# fullSketch.net
KiCad netlist of a schematic drawn in EAGLE
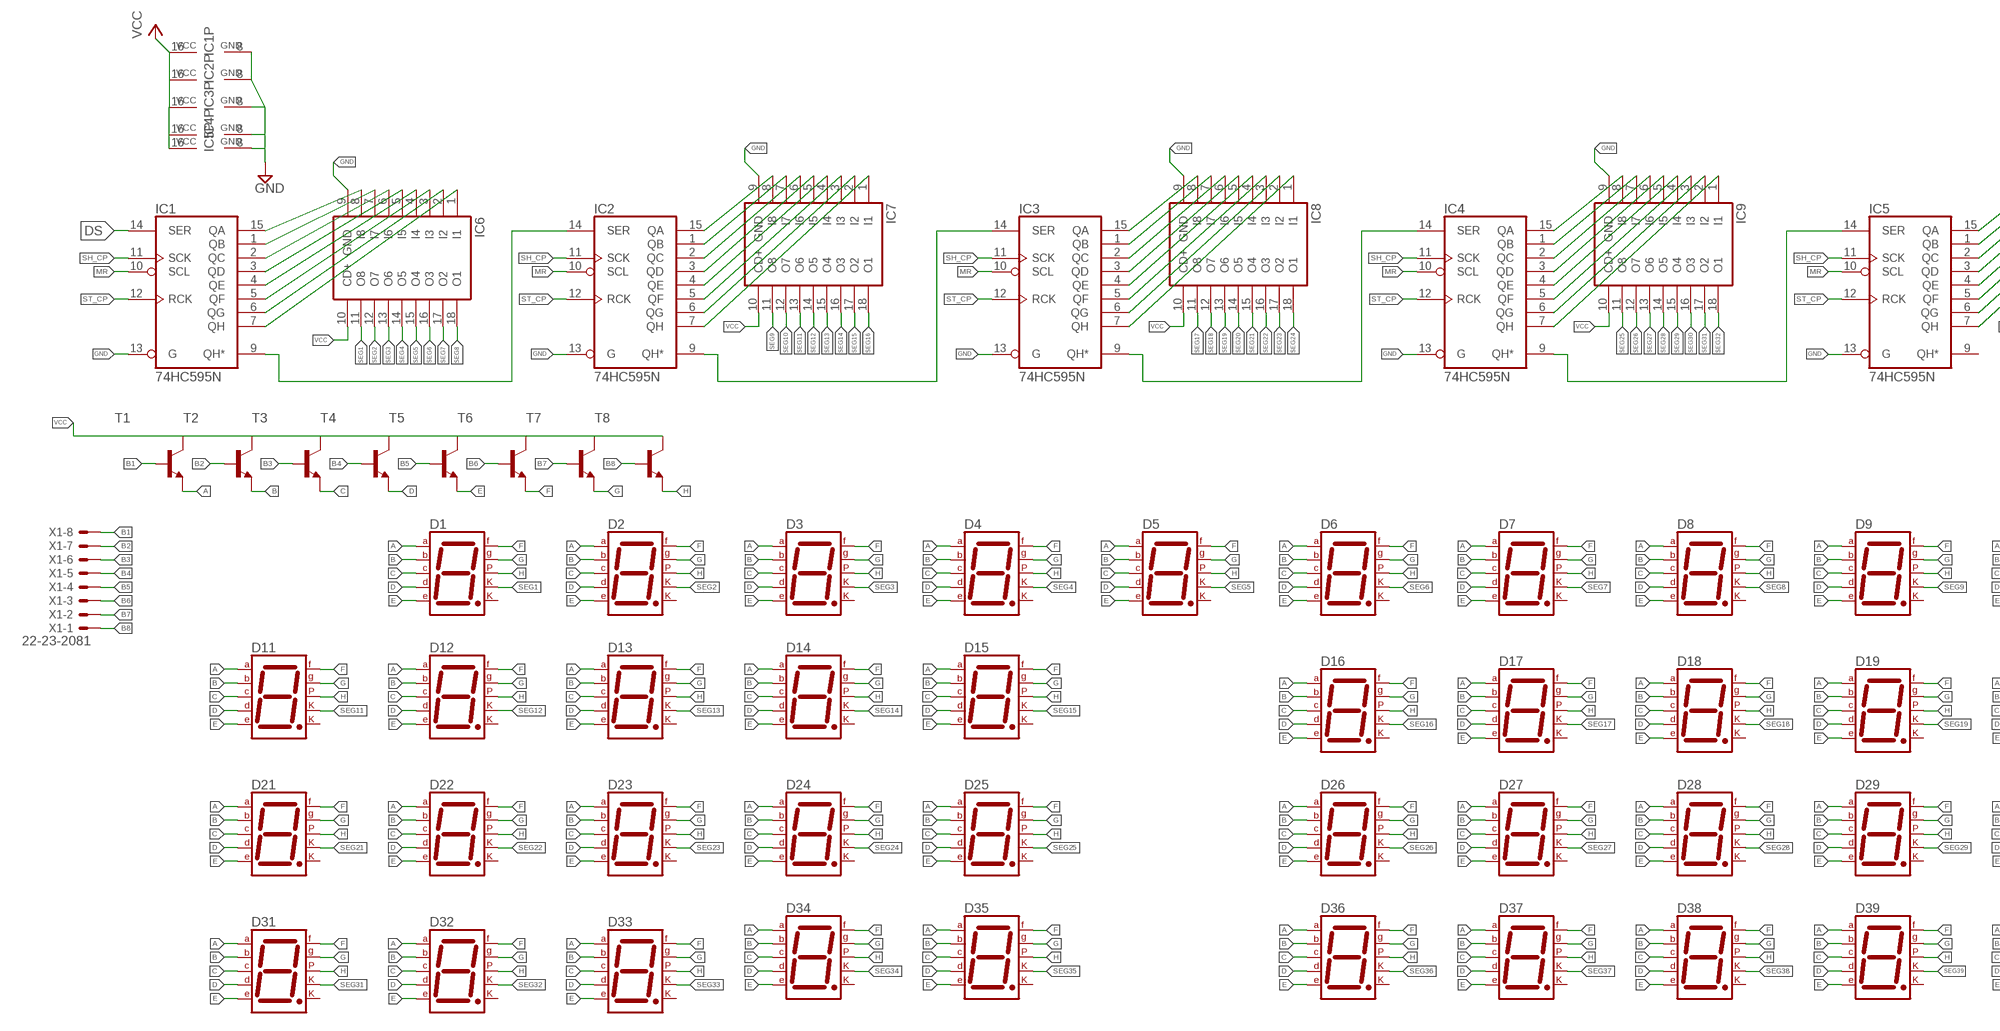
[diagram p0: schematic, sheet 1, part 1 of 2]
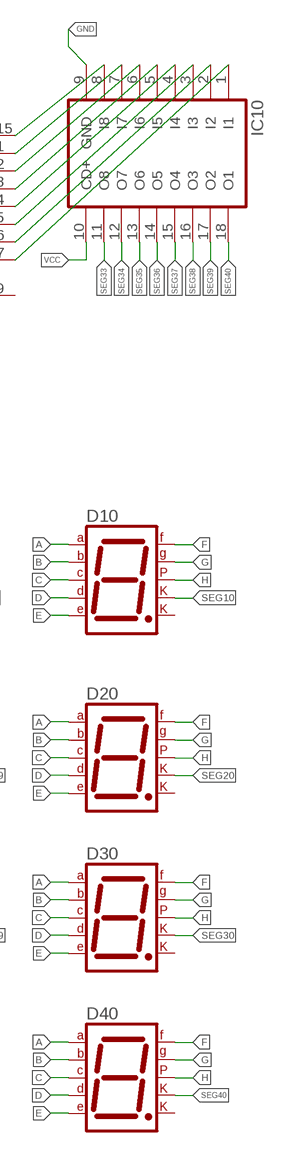
[diagram p1: schematic, sheet 1, part 2 of 2]

(export (version "E")
  (design (tool "Eeschema 10.0.6"))
  (components
    (comp (ref "D1")
      (value "7SEG-CK")
      (footprint "eagle-import:7SEG-13")
      (libsource (lib "eagle-import") (part "7SEG-CK"))
    )
    (comp (ref "D2")
      (value "7SEG-CK")
      (footprint "eagle-import:7SEG-13")
      (libsource (lib "eagle-import") (part "7SEG-CK"))
    )
    (comp (ref "D3")
      (value "7SEG-CK")
      (footprint "eagle-import:7SEG-13")
      (libsource (lib "eagle-import") (part "7SEG-CK"))
    )
    (comp (ref "D4")
      (value "7SEG-CK")
      (footprint "eagle-import:7SEG-13")
      (libsource (lib "eagle-import") (part "7SEG-CK"))
    )
    (comp (ref "D5")
      (value "7SEG-CK")
      (footprint "eagle-import:7SEG-13")
      (libsource (lib "eagle-import") (part "7SEG-CK"))
    )
    (comp (ref "D6")
      (value "7SEG-CK")
      (footprint "eagle-import:7SEG-13")
      (libsource (lib "eagle-import") (part "7SEG-CK"))
    )
    (comp (ref "D7")
      (value "7SEG-CK")
      (footprint "eagle-import:7SEG-13")
      (libsource (lib "eagle-import") (part "7SEG-CK"))
    )
    (comp (ref "D8")
      (value "7SEG-CK")
      (footprint "eagle-import:7SEG-13")
      (libsource (lib "eagle-import") (part "7SEG-CK"))
    )
    (comp (ref "D9")
      (value "7SEG-CK")
      (footprint "eagle-import:7SEG-13")
      (libsource (lib "eagle-import") (part "7SEG-CK"))
    )
    (comp (ref "D10")
      (value "7SEG-CK")
      (footprint "eagle-import:7SEG-13")
      (libsource (lib "eagle-import") (part "7SEG-CK"))
    )
    (comp (ref "D11")
      (value "7SEG-CK")
      (footprint "eagle-import:7SEG-13")
      (libsource (lib "eagle-import") (part "7SEG-CK"))
    )
    (comp (ref "D12")
      (value "7SEG-CK")
      (footprint "eagle-import:7SEG-13")
      (libsource (lib "eagle-import") (part "7SEG-CK"))
    )
    (comp (ref "D13")
      (value "7SEG-CK")
      (footprint "eagle-import:7SEG-13")
      (libsource (lib "eagle-import") (part "7SEG-CK"))
    )
    (comp (ref "D14")
      (value "7SEG-CK")
      (footprint "eagle-import:7SEG-13")
      (libsource (lib "eagle-import") (part "7SEG-CK"))
    )
    (comp (ref "D15")
      (value "7SEG-CK")
      (footprint "eagle-import:7SEG-13")
      (libsource (lib "eagle-import") (part "7SEG-CK"))
    )
    (comp (ref "D16")
      (value "7SEG-CK")
      (footprint "eagle-import:7SEG-13")
      (libsource (lib "eagle-import") (part "7SEG-CK"))
    )
    (comp (ref "D17")
      (value "7SEG-CK")
      (footprint "eagle-import:7SEG-13")
      (libsource (lib "eagle-import") (part "7SEG-CK"))
    )
    (comp (ref "D18")
      (value "7SEG-CK")
      (footprint "eagle-import:7SEG-13")
      (libsource (lib "eagle-import") (part "7SEG-CK"))
    )
    (comp (ref "D19")
      (value "7SEG-CK")
      (footprint "eagle-import:7SEG-13")
      (libsource (lib "eagle-import") (part "7SEG-CK"))
    )
    (comp (ref "D20")
      (value "7SEG-CK")
      (footprint "eagle-import:7SEG-13")
      (libsource (lib "eagle-import") (part "7SEG-CK"))
    )
    (comp (ref "D21")
      (value "7SEG-CK")
      (footprint "eagle-import:7SEG-13")
      (libsource (lib "eagle-import") (part "7SEG-CK"))
    )
    (comp (ref "D22")
      (value "7SEG-CK")
      (footprint "eagle-import:7SEG-13")
      (libsource (lib "eagle-import") (part "7SEG-CK"))
    )
    (comp (ref "D23")
      (value "7SEG-CK")
      (footprint "eagle-import:7SEG-13")
      (libsource (lib "eagle-import") (part "7SEG-CK"))
    )
    (comp (ref "D24")
      (value "7SEG-CK")
      (footprint "eagle-import:7SEG-13")
      (libsource (lib "eagle-import") (part "7SEG-CK"))
    )
    (comp (ref "D25")
      (value "7SEG-CK")
      (footprint "eagle-import:7SEG-13")
      (libsource (lib "eagle-import") (part "7SEG-CK"))
    )
    (comp (ref "D26")
      (value "7SEG-CK")
      (footprint "eagle-import:7SEG-13")
      (libsource (lib "eagle-import") (part "7SEG-CK"))
    )
    (comp (ref "D27")
      (value "7SEG-CK")
      (footprint "eagle-import:7SEG-13")
      (libsource (lib "eagle-import") (part "7SEG-CK"))
    )
    (comp (ref "D28")
      (value "7SEG-CK")
      (footprint "eagle-import:7SEG-13")
      (libsource (lib "eagle-import") (part "7SEG-CK"))
    )
    (comp (ref "D29")
      (value "7SEG-CK")
      (footprint "eagle-import:7SEG-13")
      (libsource (lib "eagle-import") (part "7SEG-CK"))
    )
    (comp (ref "D30")
      (value "7SEG-CK")
      (footprint "eagle-import:7SEG-13")
      (libsource (lib "eagle-import") (part "7SEG-CK"))
    )
    (comp (ref "D31")
      (value "7SEG-CK")
      (footprint "eagle-import:7SEG-13")
      (libsource (lib "eagle-import") (part "7SEG-CK"))
    )
    (comp (ref "D32")
      (value "7SEG-CK")
      (footprint "eagle-import:7SEG-13")
      (libsource (lib "eagle-import") (part "7SEG-CK"))
    )
    (comp (ref "D33")
      (value "7SEG-CK")
      (footprint "eagle-import:7SEG-13")
      (libsource (lib "eagle-import") (part "7SEG-CK"))
    )
    (comp (ref "D34")
      (value "7SEG-CK")
      (footprint "eagle-import:7SEG-13")
      (libsource (lib "eagle-import") (part "7SEG-CK"))
    )
    (comp (ref "D35")
      (value "7SEG-CK")
      (footprint "eagle-import:7SEG-13")
      (libsource (lib "eagle-import") (part "7SEG-CK"))
    )
    (comp (ref "D36")
      (value "7SEG-CK")
      (footprint "eagle-import:7SEG-13")
      (libsource (lib "eagle-import") (part "7SEG-CK"))
    )
    (comp (ref "D37")
      (value "7SEG-CK")
      (footprint "eagle-import:7SEG-13")
      (libsource (lib "eagle-import") (part "7SEG-CK"))
    )
    (comp (ref "D38")
      (value "7SEG-CK")
      (footprint "eagle-import:7SEG-13")
      (libsource (lib "eagle-import") (part "7SEG-CK"))
    )
    (comp (ref "D39")
      (value "7SEG-CK")
      (footprint "eagle-import:7SEG-13")
      (libsource (lib "eagle-import") (part "7SEG-CK"))
    )
    (comp (ref "D40")
      (value "7SEG-CK")
      (footprint "eagle-import:7SEG-13")
      (libsource (lib "eagle-import") (part "7SEG-CK"))
    )
    (comp (ref "IC1")
      (value "74HC595N")
      (footprint "eagle-import:DIL16")
      (libsource (lib "eagle-import") (part "74595NHC"))
    )
    (comp (ref "IC2")
      (value "74HC595N")
      (footprint "eagle-import:DIL16")
      (libsource (lib "eagle-import") (part "74595NHC"))
    )
    (comp (ref "IC3")
      (value "74HC595N")
      (footprint "eagle-import:DIL16")
      (libsource (lib "eagle-import") (part "74595NHC"))
    )
    (comp (ref "IC4")
      (value "74HC595N")
      (footprint "eagle-import:DIL16")
      (libsource (lib "eagle-import") (part "74595NHC"))
    )
    (comp (ref "IC5")
      (value "74HC595N")
      (footprint "eagle-import:DIL16")
      (libsource (lib "eagle-import") (part "74595NHC"))
    )
    (comp (ref "IC6")
      (value "ULN2803A")
      (footprint "eagle-import:DIL18")
      (libsource (lib "eagle-import") (part "ULN2803A"))
    )
    (comp (ref "IC7")
      (value "ULN2803A")
      (footprint "eagle-import:DIL18")
      (libsource (lib "eagle-import") (part "ULN2803A"))
    )
    (comp (ref "IC8")
      (value "ULN2803A")
      (footprint "eagle-import:DIL18")
      (libsource (lib "eagle-import") (part "ULN2803A"))
    )
    (comp (ref "IC9")
      (value "ULN2803A")
      (footprint "eagle-import:DIL18")
      (libsource (lib "eagle-import") (part "ULN2803A"))
    )
    (comp (ref "IC10")
      (value "ULN2803A")
      (footprint "eagle-import:DIL18")
      (libsource (lib "eagle-import") (part "ULN2803A"))
    )
    (comp (ref "T1")
      (value "-NPN-TO92")
      (footprint "eagle-import:TO92")
      (libsource (lib "eagle-import") (part "-NPN-TO92"))
    )
    (comp (ref "T2")
      (value "-NPN-TO92")
      (footprint "eagle-import:TO92")
      (libsource (lib "eagle-import") (part "-NPN-TO92"))
    )
    (comp (ref "T3")
      (value "-NPN-TO92")
      (footprint "eagle-import:TO92")
      (libsource (lib "eagle-import") (part "-NPN-TO92"))
    )
    (comp (ref "T4")
      (value "-NPN-TO92")
      (footprint "eagle-import:TO92")
      (libsource (lib "eagle-import") (part "-NPN-TO92"))
    )
    (comp (ref "T5")
      (value "-NPN-TO92")
      (footprint "eagle-import:TO92")
      (libsource (lib "eagle-import") (part "-NPN-TO92"))
    )
    (comp (ref "T6")
      (value "-NPN-TO92")
      (footprint "eagle-import:TO92")
      (libsource (lib "eagle-import") (part "-NPN-TO92"))
    )
    (comp (ref "T7")
      (value "-NPN-TO92")
      (footprint "eagle-import:TO92")
      (libsource (lib "eagle-import") (part "-NPN-TO92"))
    )
    (comp (ref "T8")
      (value "-NPN-TO92")
      (footprint "eagle-import:TO92")
      (libsource (lib "eagle-import") (part "-NPN-TO92"))
    )
    (comp (ref "X1")
      (value "22-23-2081")
      (footprint "eagle-import:22-23-2081")
      (fields (field (name "MF") "MOLEX"))
      (libsource (lib "eagle-import") (part "22-23-2081"))
    )
  )
  (nets
    (net (code "1") (name "A") (class "Default")
      (node (ref "D1") (pin "7") (pinfunction "A_7") (pintype "passive"))
      (node (ref "D10") (pin "7") (pinfunction "A_7") (pintype "passive"))
      (node (ref "D11") (pin "7") (pinfunction "A_7") (pintype "passive"))
      (node (ref "D12") (pin "7") (pinfunction "A_7") (pintype "passive"))
      (node (ref "D13") (pin "7") (pinfunction "A_7") (pintype "passive"))
      (node (ref "D14") (pin "7") (pinfunction "A_7") (pintype "passive"))
      (node (ref "D15") (pin "7") (pinfunction "A_7") (pintype "passive"))
      (node (ref "D16") (pin "7") (pinfunction "A_7") (pintype "passive"))
      (node (ref "D17") (pin "7") (pinfunction "A_7") (pintype "passive"))
      (node (ref "D18") (pin "7") (pinfunction "A_7") (pintype "passive"))
      (node (ref "D19") (pin "7") (pinfunction "A_7") (pintype "passive"))
      (node (ref "D2") (pin "7") (pinfunction "A_7") (pintype "passive"))
      (node (ref "D20") (pin "7") (pinfunction "A_7") (pintype "passive"))
      (node (ref "D21") (pin "7") (pinfunction "A_7") (pintype "passive"))
      (node (ref "D22") (pin "7") (pinfunction "A_7") (pintype "passive"))
      (node (ref "D23") (pin "7") (pinfunction "A_7") (pintype "passive"))
      (node (ref "D24") (pin "7") (pinfunction "A_7") (pintype "passive"))
      (node (ref "D25") (pin "7") (pinfunction "A_7") (pintype "passive"))
      (node (ref "D26") (pin "7") (pinfunction "A_7") (pintype "passive"))
      (node (ref "D27") (pin "7") (pinfunction "A_7") (pintype "passive"))
      (node (ref "D28") (pin "7") (pinfunction "A_7") (pintype "passive"))
      (node (ref "D29") (pin "7") (pinfunction "A_7") (pintype "passive"))
      (node (ref "D3") (pin "7") (pinfunction "A_7") (pintype "passive"))
      (node (ref "D30") (pin "7") (pinfunction "A_7") (pintype "passive"))
      (node (ref "D31") (pin "7") (pinfunction "A_7") (pintype "passive"))
      (node (ref "D32") (pin "7") (pinfunction "A_7") (pintype "passive"))
      (node (ref "D33") (pin "7") (pinfunction "A_7") (pintype "passive"))
      (node (ref "D34") (pin "7") (pinfunction "A_7") (pintype "passive"))
      (node (ref "D35") (pin "7") (pinfunction "A_7") (pintype "passive"))
      (node (ref "D36") (pin "7") (pinfunction "A_7") (pintype "passive"))
      (node (ref "D37") (pin "7") (pinfunction "A_7") (pintype "passive"))
      (node (ref "D38") (pin "7") (pinfunction "A_7") (pintype "passive"))
      (node (ref "D39") (pin "7") (pinfunction "A_7") (pintype "passive"))
      (node (ref "D4") (pin "7") (pinfunction "A_7") (pintype "passive"))
      (node (ref "D40") (pin "7") (pinfunction "A_7") (pintype "passive"))
      (node (ref "D5") (pin "7") (pinfunction "A_7") (pintype "passive"))
      (node (ref "D6") (pin "7") (pinfunction "A_7") (pintype "passive"))
      (node (ref "D7") (pin "7") (pinfunction "A_7") (pintype "passive"))
      (node (ref "D8") (pin "7") (pinfunction "A_7") (pintype "passive"))
      (node (ref "D9") (pin "7") (pinfunction "A_7") (pintype "passive"))
      (node (ref "T1") (pin "1") (pinfunction "E_1") (pintype "passive"))
    )
    (net (code "2") (name "B") (class "Default")
      (node (ref "D1") (pin "6") (pinfunction "B_6") (pintype "passive"))
      (node (ref "D10") (pin "6") (pinfunction "B_6") (pintype "passive"))
      (node (ref "D11") (pin "6") (pinfunction "B_6") (pintype "passive"))
      (node (ref "D12") (pin "6") (pinfunction "B_6") (pintype "passive"))
      (node (ref "D13") (pin "6") (pinfunction "B_6") (pintype "passive"))
      (node (ref "D14") (pin "6") (pinfunction "B_6") (pintype "passive"))
      (node (ref "D15") (pin "6") (pinfunction "B_6") (pintype "passive"))
      (node (ref "D16") (pin "6") (pinfunction "B_6") (pintype "passive"))
      (node (ref "D17") (pin "6") (pinfunction "B_6") (pintype "passive"))
      (node (ref "D18") (pin "6") (pinfunction "B_6") (pintype "passive"))
      (node (ref "D19") (pin "6") (pinfunction "B_6") (pintype "passive"))
      (node (ref "D2") (pin "6") (pinfunction "B_6") (pintype "passive"))
      (node (ref "D20") (pin "6") (pinfunction "B_6") (pintype "passive"))
      (node (ref "D21") (pin "6") (pinfunction "B_6") (pintype "passive"))
      (node (ref "D22") (pin "6") (pinfunction "B_6") (pintype "passive"))
      (node (ref "D23") (pin "6") (pinfunction "B_6") (pintype "passive"))
      (node (ref "D24") (pin "6") (pinfunction "B_6") (pintype "passive"))
      (node (ref "D25") (pin "6") (pinfunction "B_6") (pintype "passive"))
      (node (ref "D26") (pin "6") (pinfunction "B_6") (pintype "passive"))
      (node (ref "D27") (pin "6") (pinfunction "B_6") (pintype "passive"))
      (node (ref "D28") (pin "6") (pinfunction "B_6") (pintype "passive"))
      (node (ref "D29") (pin "6") (pinfunction "B_6") (pintype "passive"))
      (node (ref "D3") (pin "6") (pinfunction "B_6") (pintype "passive"))
      (node (ref "D30") (pin "6") (pinfunction "B_6") (pintype "passive"))
      (node (ref "D31") (pin "6") (pinfunction "B_6") (pintype "passive"))
      (node (ref "D32") (pin "6") (pinfunction "B_6") (pintype "passive"))
      (node (ref "D33") (pin "6") (pinfunction "B_6") (pintype "passive"))
      (node (ref "D34") (pin "6") (pinfunction "B_6") (pintype "passive"))
      (node (ref "D35") (pin "6") (pinfunction "B_6") (pintype "passive"))
      (node (ref "D36") (pin "6") (pinfunction "B_6") (pintype "passive"))
      (node (ref "D37") (pin "6") (pinfunction "B_6") (pintype "passive"))
      (node (ref "D38") (pin "6") (pinfunction "B_6") (pintype "passive"))
      (node (ref "D39") (pin "6") (pinfunction "B_6") (pintype "passive"))
      (node (ref "D4") (pin "6") (pinfunction "B_6") (pintype "passive"))
      (node (ref "D40") (pin "6") (pinfunction "B_6") (pintype "passive"))
      (node (ref "D5") (pin "6") (pinfunction "B_6") (pintype "passive"))
      (node (ref "D6") (pin "6") (pinfunction "B_6") (pintype "passive"))
      (node (ref "D7") (pin "6") (pinfunction "B_6") (pintype "passive"))
      (node (ref "D8") (pin "6") (pinfunction "B_6") (pintype "passive"))
      (node (ref "D9") (pin "6") (pinfunction "B_6") (pintype "passive"))
      (node (ref "T2") (pin "1") (pinfunction "E_1") (pintype "passive"))
    )
    (net (code "3") (name "B1") (class "Default")
      (node (ref "T1") (pin "2") (pinfunction "B_2") (pintype "passive"))
      (node (ref "X1") (pin "8") (pinfunction "S_8") (pintype "passive"))
    )
    (net (code "4") (name "B2") (class "Default")
      (node (ref "T2") (pin "2") (pinfunction "B_2") (pintype "passive"))
      (node (ref "X1") (pin "7") (pinfunction "S_7") (pintype "passive"))
    )
    (net (code "5") (name "B3") (class "Default")
      (node (ref "T3") (pin "2") (pinfunction "B_2") (pintype "passive"))
      (node (ref "X1") (pin "6") (pinfunction "S_6") (pintype "passive"))
    )
    (net (code "6") (name "B4") (class "Default")
      (node (ref "T4") (pin "2") (pinfunction "B_2") (pintype "passive"))
      (node (ref "X1") (pin "5") (pinfunction "S_5") (pintype "passive"))
    )
    (net (code "7") (name "B5") (class "Default")
      (node (ref "T5") (pin "2") (pinfunction "B_2") (pintype "passive"))
      (node (ref "X1") (pin "4") (pinfunction "S_4") (pintype "passive"))
    )
    (net (code "8") (name "B6") (class "Default")
      (node (ref "T6") (pin "2") (pinfunction "B_2") (pintype "passive"))
      (node (ref "X1") (pin "3") (pinfunction "S_3") (pintype "passive"))
    )
    (net (code "9") (name "B7") (class "Default")
      (node (ref "T7") (pin "2") (pinfunction "B_2") (pintype "passive"))
      (node (ref "X1") (pin "2") (pinfunction "S_2") (pintype "passive"))
    )
    (net (code "10") (name "B8") (class "Default")
      (node (ref "T8") (pin "2") (pinfunction "B_2") (pintype "passive"))
      (node (ref "X1") (pin "1") (pinfunction "S_1") (pintype "passive"))
    )
    (net (code "11") (name "C") (class "Default")
      (node (ref "D1") (pin "4") (pinfunction "C_4") (pintype "passive"))
      (node (ref "D10") (pin "4") (pinfunction "C_4") (pintype "passive"))
      (node (ref "D11") (pin "4") (pinfunction "C_4") (pintype "passive"))
      (node (ref "D12") (pin "4") (pinfunction "C_4") (pintype "passive"))
      (node (ref "D13") (pin "4") (pinfunction "C_4") (pintype "passive"))
      (node (ref "D14") (pin "4") (pinfunction "C_4") (pintype "passive"))
      (node (ref "D15") (pin "4") (pinfunction "C_4") (pintype "passive"))
      (node (ref "D16") (pin "4") (pinfunction "C_4") (pintype "passive"))
      (node (ref "D17") (pin "4") (pinfunction "C_4") (pintype "passive"))
      (node (ref "D18") (pin "4") (pinfunction "C_4") (pintype "passive"))
      (node (ref "D19") (pin "4") (pinfunction "C_4") (pintype "passive"))
      (node (ref "D2") (pin "4") (pinfunction "C_4") (pintype "passive"))
      (node (ref "D20") (pin "4") (pinfunction "C_4") (pintype "passive"))
      (node (ref "D21") (pin "4") (pinfunction "C_4") (pintype "passive"))
      (node (ref "D22") (pin "4") (pinfunction "C_4") (pintype "passive"))
      (node (ref "D23") (pin "4") (pinfunction "C_4") (pintype "passive"))
      (node (ref "D24") (pin "4") (pinfunction "C_4") (pintype "passive"))
      (node (ref "D25") (pin "4") (pinfunction "C_4") (pintype "passive"))
      (node (ref "D26") (pin "4") (pinfunction "C_4") (pintype "passive"))
      (node (ref "D27") (pin "4") (pinfunction "C_4") (pintype "passive"))
      (node (ref "D28") (pin "4") (pinfunction "C_4") (pintype "passive"))
      (node (ref "D29") (pin "4") (pinfunction "C_4") (pintype "passive"))
      (node (ref "D3") (pin "4") (pinfunction "C_4") (pintype "passive"))
      (node (ref "D30") (pin "4") (pinfunction "C_4") (pintype "passive"))
      (node (ref "D31") (pin "4") (pinfunction "C_4") (pintype "passive"))
      (node (ref "D32") (pin "4") (pinfunction "C_4") (pintype "passive"))
      (node (ref "D33") (pin "4") (pinfunction "C_4") (pintype "passive"))
      (node (ref "D34") (pin "4") (pinfunction "C_4") (pintype "passive"))
      (node (ref "D35") (pin "4") (pinfunction "C_4") (pintype "passive"))
      (node (ref "D36") (pin "4") (pinfunction "C_4") (pintype "passive"))
      (node (ref "D37") (pin "4") (pinfunction "C_4") (pintype "passive"))
      (node (ref "D38") (pin "4") (pinfunction "C_4") (pintype "passive"))
      (node (ref "D39") (pin "4") (pinfunction "C_4") (pintype "passive"))
      (node (ref "D4") (pin "4") (pinfunction "C_4") (pintype "passive"))
      (node (ref "D40") (pin "4") (pinfunction "C_4") (pintype "passive"))
      (node (ref "D5") (pin "4") (pinfunction "C_4") (pintype "passive"))
      (node (ref "D6") (pin "4") (pinfunction "C_4") (pintype "passive"))
      (node (ref "D7") (pin "4") (pinfunction "C_4") (pintype "passive"))
      (node (ref "D8") (pin "4") (pinfunction "C_4") (pintype "passive"))
      (node (ref "D9") (pin "4") (pinfunction "C_4") (pintype "passive"))
      (node (ref "T3") (pin "1") (pinfunction "E_1") (pintype "passive"))
    )
    (net (code "12") (name "D") (class "Default")
      (node (ref "D1") (pin "2") (pinfunction "D_2") (pintype "passive"))
      (node (ref "D10") (pin "2") (pinfunction "D_2") (pintype "passive"))
      (node (ref "D11") (pin "2") (pinfunction "D_2") (pintype "passive"))
      (node (ref "D12") (pin "2") (pinfunction "D_2") (pintype "passive"))
      (node (ref "D13") (pin "2") (pinfunction "D_2") (pintype "passive"))
      (node (ref "D14") (pin "2") (pinfunction "D_2") (pintype "passive"))
      (node (ref "D15") (pin "2") (pinfunction "D_2") (pintype "passive"))
      (node (ref "D16") (pin "2") (pinfunction "D_2") (pintype "passive"))
      (node (ref "D17") (pin "2") (pinfunction "D_2") (pintype "passive"))
      (node (ref "D18") (pin "2") (pinfunction "D_2") (pintype "passive"))
      (node (ref "D19") (pin "2") (pinfunction "D_2") (pintype "passive"))
      (node (ref "D2") (pin "2") (pinfunction "D_2") (pintype "passive"))
      (node (ref "D20") (pin "2") (pinfunction "D_2") (pintype "passive"))
      (node (ref "D21") (pin "2") (pinfunction "D_2") (pintype "passive"))
      (node (ref "D22") (pin "2") (pinfunction "D_2") (pintype "passive"))
      (node (ref "D23") (pin "2") (pinfunction "D_2") (pintype "passive"))
      (node (ref "D24") (pin "2") (pinfunction "D_2") (pintype "passive"))
      (node (ref "D25") (pin "2") (pinfunction "D_2") (pintype "passive"))
      (node (ref "D26") (pin "2") (pinfunction "D_2") (pintype "passive"))
      (node (ref "D27") (pin "2") (pinfunction "D_2") (pintype "passive"))
      (node (ref "D28") (pin "2") (pinfunction "D_2") (pintype "passive"))
      (node (ref "D29") (pin "2") (pinfunction "D_2") (pintype "passive"))
      (node (ref "D3") (pin "2") (pinfunction "D_2") (pintype "passive"))
      (node (ref "D30") (pin "2") (pinfunction "D_2") (pintype "passive"))
      (node (ref "D31") (pin "2") (pinfunction "D_2") (pintype "passive"))
      (node (ref "D32") (pin "2") (pinfunction "D_2") (pintype "passive"))
      (node (ref "D33") (pin "2") (pinfunction "D_2") (pintype "passive"))
      (node (ref "D34") (pin "2") (pinfunction "D_2") (pintype "passive"))
      (node (ref "D35") (pin "2") (pinfunction "D_2") (pintype "passive"))
      (node (ref "D36") (pin "2") (pinfunction "D_2") (pintype "passive"))
      (node (ref "D37") (pin "2") (pinfunction "D_2") (pintype "passive"))
      (node (ref "D38") (pin "2") (pinfunction "D_2") (pintype "passive"))
      (node (ref "D39") (pin "2") (pinfunction "D_2") (pintype "passive"))
      (node (ref "D4") (pin "2") (pinfunction "D_2") (pintype "passive"))
      (node (ref "D40") (pin "2") (pinfunction "D_2") (pintype "passive"))
      (node (ref "D5") (pin "2") (pinfunction "D_2") (pintype "passive"))
      (node (ref "D6") (pin "2") (pinfunction "D_2") (pintype "passive"))
      (node (ref "D7") (pin "2") (pinfunction "D_2") (pintype "passive"))
      (node (ref "D8") (pin "2") (pinfunction "D_2") (pintype "passive"))
      (node (ref "D9") (pin "2") (pinfunction "D_2") (pintype "passive"))
      (node (ref "T4") (pin "1") (pinfunction "E_1") (pintype "passive"))
    )
    (net (code "13") (name "DS") (class "Default")
      (node (ref "IC1") (pin "14") (pinfunction "SER_14") (pintype "input"))
    )
    (net (code "14") (name "E") (class "Default")
      (node (ref "D1") (pin "1") (pinfunction "E_1") (pintype "passive"))
      (node (ref "D10") (pin "1") (pinfunction "E_1") (pintype "passive"))
      (node (ref "D11") (pin "1") (pinfunction "E_1") (pintype "passive"))
      (node (ref "D12") (pin "1") (pinfunction "E_1") (pintype "passive"))
      (node (ref "D13") (pin "1") (pinfunction "E_1") (pintype "passive"))
      (node (ref "D14") (pin "1") (pinfunction "E_1") (pintype "passive"))
      (node (ref "D15") (pin "1") (pinfunction "E_1") (pintype "passive"))
      (node (ref "D16") (pin "1") (pinfunction "E_1") (pintype "passive"))
      (node (ref "D17") (pin "1") (pinfunction "E_1") (pintype "passive"))
      (node (ref "D18") (pin "1") (pinfunction "E_1") (pintype "passive"))
      (node (ref "D19") (pin "1") (pinfunction "E_1") (pintype "passive"))
      (node (ref "D2") (pin "1") (pinfunction "E_1") (pintype "passive"))
      (node (ref "D20") (pin "1") (pinfunction "E_1") (pintype "passive"))
      (node (ref "D21") (pin "1") (pinfunction "E_1") (pintype "passive"))
      (node (ref "D22") (pin "1") (pinfunction "E_1") (pintype "passive"))
      (node (ref "D23") (pin "1") (pinfunction "E_1") (pintype "passive"))
      (node (ref "D24") (pin "1") (pinfunction "E_1") (pintype "passive"))
      (node (ref "D25") (pin "1") (pinfunction "E_1") (pintype "passive"))
      (node (ref "D26") (pin "1") (pinfunction "E_1") (pintype "passive"))
      (node (ref "D27") (pin "1") (pinfunction "E_1") (pintype "passive"))
      (node (ref "D28") (pin "1") (pinfunction "E_1") (pintype "passive"))
      (node (ref "D29") (pin "1") (pinfunction "E_1") (pintype "passive"))
      (node (ref "D3") (pin "1") (pinfunction "E_1") (pintype "passive"))
      (node (ref "D30") (pin "1") (pinfunction "E_1") (pintype "passive"))
      (node (ref "D31") (pin "1") (pinfunction "E_1") (pintype "passive"))
      (node (ref "D32") (pin "1") (pinfunction "E_1") (pintype "passive"))
      (node (ref "D33") (pin "1") (pinfunction "E_1") (pintype "passive"))
      (node (ref "D34") (pin "1") (pinfunction "E_1") (pintype "passive"))
      (node (ref "D35") (pin "1") (pinfunction "E_1") (pintype "passive"))
      (node (ref "D36") (pin "1") (pinfunction "E_1") (pintype "passive"))
      (node (ref "D37") (pin "1") (pinfunction "E_1") (pintype "passive"))
      (node (ref "D38") (pin "1") (pinfunction "E_1") (pintype "passive"))
      (node (ref "D39") (pin "1") (pinfunction "E_1") (pintype "passive"))
      (node (ref "D4") (pin "1") (pinfunction "E_1") (pintype "passive"))
      (node (ref "D40") (pin "1") (pinfunction "E_1") (pintype "passive"))
      (node (ref "D5") (pin "1") (pinfunction "E_1") (pintype "passive"))
      (node (ref "D6") (pin "1") (pinfunction "E_1") (pintype "passive"))
      (node (ref "D7") (pin "1") (pinfunction "E_1") (pintype "passive"))
      (node (ref "D8") (pin "1") (pinfunction "E_1") (pintype "passive"))
      (node (ref "D9") (pin "1") (pinfunction "E_1") (pintype "passive"))
      (node (ref "T5") (pin "1") (pinfunction "E_1") (pintype "passive"))
    )
    (net (code "15") (name "F") (class "Default")
      (node (ref "D1") (pin "9") (pinfunction "F_9") (pintype "passive"))
      (node (ref "D10") (pin "9") (pinfunction "F_9") (pintype "passive"))
      (node (ref "D11") (pin "9") (pinfunction "F_9") (pintype "passive"))
      (node (ref "D12") (pin "9") (pinfunction "F_9") (pintype "passive"))
      (node (ref "D13") (pin "9") (pinfunction "F_9") (pintype "passive"))
      (node (ref "D14") (pin "9") (pinfunction "F_9") (pintype "passive"))
      (node (ref "D15") (pin "9") (pinfunction "F_9") (pintype "passive"))
      (node (ref "D16") (pin "9") (pinfunction "F_9") (pintype "passive"))
      (node (ref "D17") (pin "9") (pinfunction "F_9") (pintype "passive"))
      (node (ref "D18") (pin "9") (pinfunction "F_9") (pintype "passive"))
      (node (ref "D19") (pin "9") (pinfunction "F_9") (pintype "passive"))
      (node (ref "D2") (pin "9") (pinfunction "F_9") (pintype "passive"))
      (node (ref "D20") (pin "9") (pinfunction "F_9") (pintype "passive"))
      (node (ref "D21") (pin "9") (pinfunction "F_9") (pintype "passive"))
      (node (ref "D22") (pin "9") (pinfunction "F_9") (pintype "passive"))
      (node (ref "D23") (pin "9") (pinfunction "F_9") (pintype "passive"))
      (node (ref "D24") (pin "9") (pinfunction "F_9") (pintype "passive"))
      (node (ref "D25") (pin "9") (pinfunction "F_9") (pintype "passive"))
      (node (ref "D26") (pin "9") (pinfunction "F_9") (pintype "passive"))
      (node (ref "D27") (pin "9") (pinfunction "F_9") (pintype "passive"))
      (node (ref "D28") (pin "9") (pinfunction "F_9") (pintype "passive"))
      (node (ref "D29") (pin "9") (pinfunction "F_9") (pintype "passive"))
      (node (ref "D3") (pin "9") (pinfunction "F_9") (pintype "passive"))
      (node (ref "D30") (pin "9") (pinfunction "F_9") (pintype "passive"))
      (node (ref "D31") (pin "9") (pinfunction "F_9") (pintype "passive"))
      (node (ref "D32") (pin "9") (pinfunction "F_9") (pintype "passive"))
      (node (ref "D33") (pin "9") (pinfunction "F_9") (pintype "passive"))
      (node (ref "D34") (pin "9") (pinfunction "F_9") (pintype "passive"))
      (node (ref "D35") (pin "9") (pinfunction "F_9") (pintype "passive"))
      (node (ref "D36") (pin "9") (pinfunction "F_9") (pintype "passive"))
      (node (ref "D37") (pin "9") (pinfunction "F_9") (pintype "passive"))
      (node (ref "D38") (pin "9") (pinfunction "F_9") (pintype "passive"))
      (node (ref "D39") (pin "9") (pinfunction "F_9") (pintype "passive"))
      (node (ref "D4") (pin "9") (pinfunction "F_9") (pintype "passive"))
      (node (ref "D40") (pin "9") (pinfunction "F_9") (pintype "passive"))
      (node (ref "D5") (pin "9") (pinfunction "F_9") (pintype "passive"))
      (node (ref "D6") (pin "9") (pinfunction "F_9") (pintype "passive"))
      (node (ref "D7") (pin "9") (pinfunction "F_9") (pintype "passive"))
      (node (ref "D8") (pin "9") (pinfunction "F_9") (pintype "passive"))
      (node (ref "D9") (pin "9") (pinfunction "F_9") (pintype "passive"))
      (node (ref "T6") (pin "1") (pinfunction "E_1") (pintype "passive"))
    )
    (net (code "16") (name "G") (class "Default")
      (node (ref "D1") (pin "10") (pinfunction "G_10") (pintype "passive"))
      (node (ref "D10") (pin "10") (pinfunction "G_10") (pintype "passive"))
      (node (ref "D11") (pin "10") (pinfunction "G_10") (pintype "passive"))
      (node (ref "D12") (pin "10") (pinfunction "G_10") (pintype "passive"))
      (node (ref "D13") (pin "10") (pinfunction "G_10") (pintype "passive"))
      (node (ref "D14") (pin "10") (pinfunction "G_10") (pintype "passive"))
      (node (ref "D15") (pin "10") (pinfunction "G_10") (pintype "passive"))
      (node (ref "D16") (pin "10") (pinfunction "G_10") (pintype "passive"))
      (node (ref "D17") (pin "10") (pinfunction "G_10") (pintype "passive"))
      (node (ref "D18") (pin "10") (pinfunction "G_10") (pintype "passive"))
      (node (ref "D19") (pin "10") (pinfunction "G_10") (pintype "passive"))
      (node (ref "D2") (pin "10") (pinfunction "G_10") (pintype "passive"))
      (node (ref "D20") (pin "10") (pinfunction "G_10") (pintype "passive"))
      (node (ref "D21") (pin "10") (pinfunction "G_10") (pintype "passive"))
      (node (ref "D22") (pin "10") (pinfunction "G_10") (pintype "passive"))
      (node (ref "D23") (pin "10") (pinfunction "G_10") (pintype "passive"))
      (node (ref "D24") (pin "10") (pinfunction "G_10") (pintype "passive"))
      (node (ref "D25") (pin "10") (pinfunction "G_10") (pintype "passive"))
      (node (ref "D26") (pin "10") (pinfunction "G_10") (pintype "passive"))
      (node (ref "D27") (pin "10") (pinfunction "G_10") (pintype "passive"))
      (node (ref "D28") (pin "10") (pinfunction "G_10") (pintype "passive"))
      (node (ref "D29") (pin "10") (pinfunction "G_10") (pintype "passive"))
      (node (ref "D3") (pin "10") (pinfunction "G_10") (pintype "passive"))
      (node (ref "D30") (pin "10") (pinfunction "G_10") (pintype "passive"))
      (node (ref "D31") (pin "10") (pinfunction "G_10") (pintype "passive"))
      (node (ref "D32") (pin "10") (pinfunction "G_10") (pintype "passive"))
      (node (ref "D33") (pin "10") (pinfunction "G_10") (pintype "passive"))
      (node (ref "D34") (pin "10") (pinfunction "G_10") (pintype "passive"))
      (node (ref "D35") (pin "10") (pinfunction "G_10") (pintype "passive"))
      (node (ref "D36") (pin "10") (pinfunction "G_10") (pintype "passive"))
      (node (ref "D37") (pin "10") (pinfunction "G_10") (pintype "passive"))
      (node (ref "D38") (pin "10") (pinfunction "G_10") (pintype "passive"))
      (node (ref "D39") (pin "10") (pinfunction "G_10") (pintype "passive"))
      (node (ref "D4") (pin "10") (pinfunction "G_10") (pintype "passive"))
      (node (ref "D40") (pin "10") (pinfunction "G_10") (pintype "passive"))
      (node (ref "D5") (pin "10") (pinfunction "G_10") (pintype "passive"))
      (node (ref "D6") (pin "10") (pinfunction "G_10") (pintype "passive"))
      (node (ref "D7") (pin "10") (pinfunction "G_10") (pintype "passive"))
      (node (ref "D8") (pin "10") (pinfunction "G_10") (pintype "passive"))
      (node (ref "D9") (pin "10") (pinfunction "G_10") (pintype "passive"))
      (node (ref "T7") (pin "1") (pinfunction "E_1") (pintype "passive"))
    )
    (net (code "17") (name "GND") (class "Default")
      (node (ref "IC1") (pin "13") (pinfunction "G_13") (pintype "input"))
      (node (ref "IC1") (pin "8") (pinfunction "GND_8") (pintype "power_in"))
      (node (ref "IC10") (pin "9") (pinfunction "GND_9") (pintype "power_in"))
      (node (ref "IC2") (pin "13") (pinfunction "G_13") (pintype "input"))
      (node (ref "IC2") (pin "8") (pinfunction "GND_8") (pintype "power_in"))
      (node (ref "IC3") (pin "13") (pinfunction "G_13") (pintype "input"))
      (node (ref "IC3") (pin "8") (pinfunction "GND_8") (pintype "power_in"))
      (node (ref "IC4") (pin "13") (pinfunction "G_13") (pintype "input"))
      (node (ref "IC4") (pin "8") (pinfunction "GND_8") (pintype "power_in"))
      (node (ref "IC5") (pin "13") (pinfunction "G_13") (pintype "input"))
      (node (ref "IC5") (pin "8") (pinfunction "GND_8") (pintype "power_in"))
      (node (ref "IC6") (pin "9") (pinfunction "GND_9") (pintype "power_in"))
      (node (ref "IC7") (pin "9") (pinfunction "GND_9") (pintype "power_in"))
      (node (ref "IC8") (pin "9") (pinfunction "GND_9") (pintype "power_in"))
      (node (ref "IC9") (pin "9") (pinfunction "GND_9") (pintype "power_in"))
    )
    (net (code "18") (name "H") (class "Default")
      (node (ref "D1") (pin "5") (pinfunction "DP_5") (pintype "passive"))
      (node (ref "D10") (pin "5") (pinfunction "DP_5") (pintype "passive"))
      (node (ref "D11") (pin "5") (pinfunction "DP_5") (pintype "passive"))
      (node (ref "D12") (pin "5") (pinfunction "DP_5") (pintype "passive"))
      (node (ref "D13") (pin "5") (pinfunction "DP_5") (pintype "passive"))
      (node (ref "D14") (pin "5") (pinfunction "DP_5") (pintype "passive"))
      (node (ref "D15") (pin "5") (pinfunction "DP_5") (pintype "passive"))
      (node (ref "D16") (pin "5") (pinfunction "DP_5") (pintype "passive"))
      (node (ref "D17") (pin "5") (pinfunction "DP_5") (pintype "passive"))
      (node (ref "D18") (pin "5") (pinfunction "DP_5") (pintype "passive"))
      (node (ref "D19") (pin "5") (pinfunction "DP_5") (pintype "passive"))
      (node (ref "D2") (pin "5") (pinfunction "DP_5") (pintype "passive"))
      (node (ref "D20") (pin "5") (pinfunction "DP_5") (pintype "passive"))
      (node (ref "D21") (pin "5") (pinfunction "DP_5") (pintype "passive"))
      (node (ref "D22") (pin "5") (pinfunction "DP_5") (pintype "passive"))
      (node (ref "D23") (pin "5") (pinfunction "DP_5") (pintype "passive"))
      (node (ref "D24") (pin "5") (pinfunction "DP_5") (pintype "passive"))
      (node (ref "D25") (pin "5") (pinfunction "DP_5") (pintype "passive"))
      (node (ref "D26") (pin "5") (pinfunction "DP_5") (pintype "passive"))
      (node (ref "D27") (pin "5") (pinfunction "DP_5") (pintype "passive"))
      (node (ref "D28") (pin "5") (pinfunction "DP_5") (pintype "passive"))
      (node (ref "D29") (pin "5") (pinfunction "DP_5") (pintype "passive"))
      (node (ref "D3") (pin "5") (pinfunction "DP_5") (pintype "passive"))
      (node (ref "D30") (pin "5") (pinfunction "DP_5") (pintype "passive"))
      (node (ref "D31") (pin "5") (pinfunction "DP_5") (pintype "passive"))
      (node (ref "D32") (pin "5") (pinfunction "DP_5") (pintype "passive"))
      (node (ref "D33") (pin "5") (pinfunction "DP_5") (pintype "passive"))
      (node (ref "D34") (pin "5") (pinfunction "DP_5") (pintype "passive"))
      (node (ref "D35") (pin "5") (pinfunction "DP_5") (pintype "passive"))
      (node (ref "D36") (pin "5") (pinfunction "DP_5") (pintype "passive"))
      (node (ref "D37") (pin "5") (pinfunction "DP_5") (pintype "passive"))
      (node (ref "D38") (pin "5") (pinfunction "DP_5") (pintype "passive"))
      (node (ref "D39") (pin "5") (pinfunction "DP_5") (pintype "passive"))
      (node (ref "D4") (pin "5") (pinfunction "DP_5") (pintype "passive"))
      (node (ref "D40") (pin "5") (pinfunction "DP_5") (pintype "passive"))
      (node (ref "D5") (pin "5") (pinfunction "DP_5") (pintype "passive"))
      (node (ref "D6") (pin "5") (pinfunction "DP_5") (pintype "passive"))
      (node (ref "D7") (pin "5") (pinfunction "DP_5") (pintype "passive"))
      (node (ref "D8") (pin "5") (pinfunction "DP_5") (pintype "passive"))
      (node (ref "D9") (pin "5") (pinfunction "DP_5") (pintype "passive"))
      (node (ref "T8") (pin "1") (pinfunction "E_1") (pintype "passive"))
    )
    (net (code "19") (name "MR") (class "Default")
      (node (ref "IC1") (pin "10") (pinfunction "SCL_10") (pintype "input"))
      (node (ref "IC2") (pin "10") (pinfunction "SCL_10") (pintype "input"))
      (node (ref "IC3") (pin "10") (pinfunction "SCL_10") (pintype "input"))
      (node (ref "IC4") (pin "10") (pinfunction "SCL_10") (pintype "input"))
      (node (ref "IC5") (pin "10") (pinfunction "SCL_10") (pintype "input"))
    )
    (net (code "20") (name "Net-(IC1A-QA)") (class "Default")
      (node (ref "IC1") (pin "15") (pinfunction "QA_15") (pintype "tri_state"))
      (node (ref "IC6") (pin "8") (pinfunction "I8_8") (pintype "input"))
    )
    (net (code "21") (name "Net-(IC1A-QB)") (class "Default")
      (node (ref "IC1") (pin "1") (pinfunction "QB_1") (pintype "tri_state"))
      (node (ref "IC6") (pin "7") (pinfunction "I7_7") (pintype "input"))
    )
    (net (code "22") (name "Net-(IC1A-QC)") (class "Default")
      (node (ref "IC1") (pin "2") (pinfunction "QC_2") (pintype "tri_state"))
      (node (ref "IC6") (pin "6") (pinfunction "I6_6") (pintype "input"))
    )
    (net (code "23") (name "Net-(IC1A-QD)") (class "Default")
      (node (ref "IC1") (pin "3") (pinfunction "QD_3") (pintype "tri_state"))
      (node (ref "IC6") (pin "5") (pinfunction "I5_5") (pintype "input"))
    )
    (net (code "24") (name "Net-(IC1A-QE)") (class "Default")
      (node (ref "IC1") (pin "4") (pinfunction "QE_4") (pintype "tri_state"))
      (node (ref "IC6") (pin "4") (pinfunction "I4_4") (pintype "input"))
    )
    (net (code "25") (name "Net-(IC1A-QF)") (class "Default")
      (node (ref "IC1") (pin "5") (pinfunction "QF_5") (pintype "tri_state"))
      (node (ref "IC6") (pin "3") (pinfunction "I3_3") (pintype "input"))
    )
    (net (code "26") (name "Net-(IC1A-QG)") (class "Default")
      (node (ref "IC1") (pin "6") (pinfunction "QG_6") (pintype "tri_state"))
      (node (ref "IC6") (pin "2") (pinfunction "I2_2") (pintype "input"))
    )
    (net (code "27") (name "Net-(IC1A-QH)") (class "Default")
      (node (ref "IC1") (pin "7") (pinfunction "QH_7") (pintype "tri_state"))
      (node (ref "IC6") (pin "1") (pinfunction "I1_1") (pintype "input"))
    )
    (net (code "28") (name "Net-(IC1A-QH*)") (class "Default")
      (node (ref "IC1") (pin "9") (pinfunction "QH*_9") (pintype "tri_state"))
      (node (ref "IC2") (pin "14") (pinfunction "SER_14") (pintype "input"))
    )
    (net (code "29") (name "Net-(IC2A-QA)") (class "Default")
      (node (ref "IC2") (pin "15") (pinfunction "QA_15") (pintype "tri_state"))
      (node (ref "IC7") (pin "8") (pinfunction "I8_8") (pintype "input"))
    )
    (net (code "30") (name "Net-(IC2A-QB)") (class "Default")
      (node (ref "IC2") (pin "1") (pinfunction "QB_1") (pintype "tri_state"))
      (node (ref "IC7") (pin "7") (pinfunction "I7_7") (pintype "input"))
    )
    (net (code "31") (name "Net-(IC2A-QC)") (class "Default")
      (node (ref "IC2") (pin "2") (pinfunction "QC_2") (pintype "tri_state"))
      (node (ref "IC7") (pin "6") (pinfunction "I6_6") (pintype "input"))
    )
    (net (code "32") (name "Net-(IC2A-QD)") (class "Default")
      (node (ref "IC2") (pin "3") (pinfunction "QD_3") (pintype "tri_state"))
      (node (ref "IC7") (pin "5") (pinfunction "I5_5") (pintype "input"))
    )
    (net (code "33") (name "Net-(IC2A-QE)") (class "Default")
      (node (ref "IC2") (pin "4") (pinfunction "QE_4") (pintype "tri_state"))
      (node (ref "IC7") (pin "4") (pinfunction "I4_4") (pintype "input"))
    )
    (net (code "34") (name "Net-(IC2A-QF)") (class "Default")
      (node (ref "IC2") (pin "5") (pinfunction "QF_5") (pintype "tri_state"))
      (node (ref "IC7") (pin "3") (pinfunction "I3_3") (pintype "input"))
    )
    (net (code "35") (name "Net-(IC2A-QG)") (class "Default")
      (node (ref "IC2") (pin "6") (pinfunction "QG_6") (pintype "tri_state"))
      (node (ref "IC7") (pin "2") (pinfunction "I2_2") (pintype "input"))
    )
    (net (code "36") (name "Net-(IC2A-QH)") (class "Default")
      (node (ref "IC2") (pin "7") (pinfunction "QH_7") (pintype "tri_state"))
      (node (ref "IC7") (pin "1") (pinfunction "I1_1") (pintype "input"))
    )
    (net (code "37") (name "Net-(IC2A-QH*)") (class "Default")
      (node (ref "IC2") (pin "9") (pinfunction "QH*_9") (pintype "tri_state"))
      (node (ref "IC3") (pin "14") (pinfunction "SER_14") (pintype "input"))
    )
    (net (code "38") (name "Net-(IC3A-QA)") (class "Default")
      (node (ref "IC3") (pin "15") (pinfunction "QA_15") (pintype "tri_state"))
      (node (ref "IC8") (pin "8") (pinfunction "I8_8") (pintype "input"))
    )
    (net (code "39") (name "Net-(IC3A-QB)") (class "Default")
      (node (ref "IC3") (pin "1") (pinfunction "QB_1") (pintype "tri_state"))
      (node (ref "IC8") (pin "7") (pinfunction "I7_7") (pintype "input"))
    )
    (net (code "40") (name "Net-(IC3A-QC)") (class "Default")
      (node (ref "IC3") (pin "2") (pinfunction "QC_2") (pintype "tri_state"))
      (node (ref "IC8") (pin "6") (pinfunction "I6_6") (pintype "input"))
    )
    (net (code "41") (name "Net-(IC3A-QD)") (class "Default")
      (node (ref "IC3") (pin "3") (pinfunction "QD_3") (pintype "tri_state"))
      (node (ref "IC8") (pin "5") (pinfunction "I5_5") (pintype "input"))
    )
    (net (code "42") (name "Net-(IC3A-QE)") (class "Default")
      (node (ref "IC3") (pin "4") (pinfunction "QE_4") (pintype "tri_state"))
      (node (ref "IC8") (pin "4") (pinfunction "I4_4") (pintype "input"))
    )
    (net (code "43") (name "Net-(IC3A-QF)") (class "Default")
      (node (ref "IC3") (pin "5") (pinfunction "QF_5") (pintype "tri_state"))
      (node (ref "IC8") (pin "3") (pinfunction "I3_3") (pintype "input"))
    )
    (net (code "44") (name "Net-(IC3A-QG)") (class "Default")
      (node (ref "IC3") (pin "6") (pinfunction "QG_6") (pintype "tri_state"))
      (node (ref "IC8") (pin "2") (pinfunction "I2_2") (pintype "input"))
    )
    (net (code "45") (name "Net-(IC3A-QH)") (class "Default")
      (node (ref "IC3") (pin "7") (pinfunction "QH_7") (pintype "tri_state"))
      (node (ref "IC8") (pin "1") (pinfunction "I1_1") (pintype "input"))
    )
    (net (code "46") (name "Net-(IC3A-QH*)") (class "Default")
      (node (ref "IC3") (pin "9") (pinfunction "QH*_9") (pintype "tri_state"))
      (node (ref "IC4") (pin "14") (pinfunction "SER_14") (pintype "input"))
    )
    (net (code "47") (name "Net-(IC4A-QA)") (class "Default")
      (node (ref "IC4") (pin "15") (pinfunction "QA_15") (pintype "tri_state"))
      (node (ref "IC9") (pin "8") (pinfunction "I8_8") (pintype "input"))
    )
    (net (code "48") (name "Net-(IC4A-QB)") (class "Default")
      (node (ref "IC4") (pin "1") (pinfunction "QB_1") (pintype "tri_state"))
      (node (ref "IC9") (pin "7") (pinfunction "I7_7") (pintype "input"))
    )
    (net (code "49") (name "Net-(IC4A-QC)") (class "Default")
      (node (ref "IC4") (pin "2") (pinfunction "QC_2") (pintype "tri_state"))
      (node (ref "IC9") (pin "6") (pinfunction "I6_6") (pintype "input"))
    )
    (net (code "50") (name "Net-(IC4A-QD)") (class "Default")
      (node (ref "IC4") (pin "3") (pinfunction "QD_3") (pintype "tri_state"))
      (node (ref "IC9") (pin "5") (pinfunction "I5_5") (pintype "input"))
    )
    (net (code "51") (name "Net-(IC4A-QE)") (class "Default")
      (node (ref "IC4") (pin "4") (pinfunction "QE_4") (pintype "tri_state"))
      (node (ref "IC9") (pin "4") (pinfunction "I4_4") (pintype "input"))
    )
    (net (code "52") (name "Net-(IC4A-QF)") (class "Default")
      (node (ref "IC4") (pin "5") (pinfunction "QF_5") (pintype "tri_state"))
      (node (ref "IC9") (pin "3") (pinfunction "I3_3") (pintype "input"))
    )
    (net (code "53") (name "Net-(IC4A-QG)") (class "Default")
      (node (ref "IC4") (pin "6") (pinfunction "QG_6") (pintype "tri_state"))
      (node (ref "IC9") (pin "2") (pinfunction "I2_2") (pintype "input"))
    )
    (net (code "54") (name "Net-(IC4A-QH)") (class "Default")
      (node (ref "IC4") (pin "7") (pinfunction "QH_7") (pintype "tri_state"))
      (node (ref "IC9") (pin "1") (pinfunction "I1_1") (pintype "input"))
    )
    (net (code "55") (name "Net-(IC4A-QH*)") (class "Default")
      (node (ref "IC4") (pin "9") (pinfunction "QH*_9") (pintype "tri_state"))
      (node (ref "IC5") (pin "14") (pinfunction "SER_14") (pintype "input"))
    )
    (net (code "56") (name "Net-(IC10-I1)") (class "Default")
      (node (ref "IC10") (pin "1") (pinfunction "I1_1") (pintype "input"))
      (node (ref "IC5") (pin "7") (pinfunction "QH_7") (pintype "tri_state"))
    )
    (net (code "57") (name "Net-(IC10-I2)") (class "Default")
      (node (ref "IC10") (pin "2") (pinfunction "I2_2") (pintype "input"))
      (node (ref "IC5") (pin "6") (pinfunction "QG_6") (pintype "tri_state"))
    )
    (net (code "58") (name "Net-(IC10-I3)") (class "Default")
      (node (ref "IC10") (pin "3") (pinfunction "I3_3") (pintype "input"))
      (node (ref "IC5") (pin "5") (pinfunction "QF_5") (pintype "tri_state"))
    )
    (net (code "59") (name "Net-(IC10-I4)") (class "Default")
      (node (ref "IC10") (pin "4") (pinfunction "I4_4") (pintype "input"))
      (node (ref "IC5") (pin "4") (pinfunction "QE_4") (pintype "tri_state"))
    )
    (net (code "60") (name "Net-(IC10-I5)") (class "Default")
      (node (ref "IC10") (pin "5") (pinfunction "I5_5") (pintype "input"))
      (node (ref "IC5") (pin "3") (pinfunction "QD_3") (pintype "tri_state"))
    )
    (net (code "61") (name "Net-(IC10-I6)") (class "Default")
      (node (ref "IC10") (pin "6") (pinfunction "I6_6") (pintype "input"))
      (node (ref "IC5") (pin "2") (pinfunction "QC_2") (pintype "tri_state"))
    )
    (net (code "62") (name "Net-(IC10-I7)") (class "Default")
      (node (ref "IC10") (pin "7") (pinfunction "I7_7") (pintype "input"))
      (node (ref "IC5") (pin "1") (pinfunction "QB_1") (pintype "tri_state"))
    )
    (net (code "63") (name "Net-(IC10-I8)") (class "Default")
      (node (ref "IC10") (pin "8") (pinfunction "I8_8") (pintype "input"))
      (node (ref "IC5") (pin "15") (pinfunction "QA_15") (pintype "tri_state"))
    )
    (net (code "64") (name "SEG1") (class "Default")
      (node (ref "D1") (pin "3") (pinfunction "CK1_3") (pintype "passive"))
      (node (ref "IC6") (pin "11") (pinfunction "O8_11") (pintype "open_collector"))
    )
    (net (code "65") (name "SEG2") (class "Default")
      (node (ref "D2") (pin "3") (pinfunction "CK1_3") (pintype "passive"))
      (node (ref "IC6") (pin "12") (pinfunction "O7_12") (pintype "open_collector"))
    )
    (net (code "66") (name "SEG3") (class "Default")
      (node (ref "D3") (pin "3") (pinfunction "CK1_3") (pintype "passive"))
      (node (ref "IC6") (pin "13") (pinfunction "O6_13") (pintype "open_collector"))
    )
    (net (code "67") (name "SEG4") (class "Default")
      (node (ref "D4") (pin "3") (pinfunction "CK1_3") (pintype "passive"))
      (node (ref "IC6") (pin "14") (pinfunction "O5_14") (pintype "open_collector"))
    )
    (net (code "68") (name "SEG5") (class "Default")
      (node (ref "D5") (pin "3") (pinfunction "CK1_3") (pintype "passive"))
      (node (ref "IC6") (pin "15") (pinfunction "O4_15") (pintype "open_collector"))
    )
    (net (code "69") (name "SEG6") (class "Default")
      (node (ref "D6") (pin "3") (pinfunction "CK1_3") (pintype "passive"))
      (node (ref "IC6") (pin "16") (pinfunction "O3_16") (pintype "open_collector"))
    )
    (net (code "70") (name "SEG7") (class "Default")
      (node (ref "D7") (pin "3") (pinfunction "CK1_3") (pintype "passive"))
      (node (ref "IC6") (pin "17") (pinfunction "O2_17") (pintype "open_collector"))
    )
    (net (code "71") (name "SEG8") (class "Default")
      (node (ref "D8") (pin "3") (pinfunction "CK1_3") (pintype "passive"))
      (node (ref "IC6") (pin "18") (pinfunction "O1_18") (pintype "open_collector"))
    )
    (net (code "72") (name "SEG9") (class "Default")
      (node (ref "D9") (pin "3") (pinfunction "CK1_3") (pintype "passive"))
      (node (ref "IC7") (pin "11") (pinfunction "O8_11") (pintype "open_collector"))
    )
    (net (code "73") (name "SEG10") (class "Default")
      (node (ref "D10") (pin "3") (pinfunction "CK1_3") (pintype "passive"))
      (node (ref "IC7") (pin "12") (pinfunction "O7_12") (pintype "open_collector"))
    )
    (net (code "74") (name "SEG11") (class "Default")
      (node (ref "D11") (pin "3") (pinfunction "CK1_3") (pintype "passive"))
      (node (ref "IC7") (pin "13") (pinfunction "O6_13") (pintype "open_collector"))
    )
    (net (code "75") (name "SEG12") (class "Default")
      (node (ref "D12") (pin "3") (pinfunction "CK1_3") (pintype "passive"))
      (node (ref "IC7") (pin "14") (pinfunction "O5_14") (pintype "open_collector"))
    )
    (net (code "76") (name "SEG13") (class "Default")
      (node (ref "D13") (pin "3") (pinfunction "CK1_3") (pintype "passive"))
      (node (ref "IC7") (pin "15") (pinfunction "O4_15") (pintype "open_collector"))
    )
    (net (code "77") (name "SEG14") (class "Default")
      (node (ref "D14") (pin "3") (pinfunction "CK1_3") (pintype "passive"))
      (node (ref "IC7") (pin "16") (pinfunction "O3_16") (pintype "open_collector"))
    )
    (net (code "78") (name "SEG15") (class "Default")
      (node (ref "D15") (pin "3") (pinfunction "CK1_3") (pintype "passive"))
      (node (ref "IC7") (pin "17") (pinfunction "O2_17") (pintype "open_collector"))
    )
    (net (code "79") (name "SEG16") (class "Default")
      (node (ref "D16") (pin "3") (pinfunction "CK1_3") (pintype "passive"))
      (node (ref "IC7") (pin "18") (pinfunction "O1_18") (pintype "open_collector"))
    )
    (net (code "80") (name "SEG17") (class "Default")
      (node (ref "D17") (pin "3") (pinfunction "CK1_3") (pintype "passive"))
      (node (ref "IC8") (pin "11") (pinfunction "O8_11") (pintype "open_collector"))
    )
    (net (code "81") (name "SEG18") (class "Default")
      (node (ref "D18") (pin "3") (pinfunction "CK1_3") (pintype "passive"))
      (node (ref "IC8") (pin "12") (pinfunction "O7_12") (pintype "open_collector"))
    )
    (net (code "82") (name "SEG19") (class "Default")
      (node (ref "D19") (pin "3") (pinfunction "CK1_3") (pintype "passive"))
      (node (ref "IC8") (pin "13") (pinfunction "O6_13") (pintype "open_collector"))
    )
    (net (code "83") (name "SEG20") (class "Default")
      (node (ref "D20") (pin "3") (pinfunction "CK1_3") (pintype "passive"))
      (node (ref "IC8") (pin "14") (pinfunction "O5_14") (pintype "open_collector"))
    )
    (net (code "84") (name "SEG21") (class "Default")
      (node (ref "D21") (pin "3") (pinfunction "CK1_3") (pintype "passive"))
      (node (ref "IC8") (pin "15") (pinfunction "O4_15") (pintype "open_collector"))
    )
    (net (code "85") (name "SEG22") (class "Default")
      (node (ref "D22") (pin "3") (pinfunction "CK1_3") (pintype "passive"))
      (node (ref "IC8") (pin "16") (pinfunction "O3_16") (pintype "open_collector"))
    )
    (net (code "86") (name "SEG23") (class "Default")
      (node (ref "D23") (pin "3") (pinfunction "CK1_3") (pintype "passive"))
      (node (ref "IC8") (pin "17") (pinfunction "O2_17") (pintype "open_collector"))
    )
    (net (code "87") (name "SEG24") (class "Default")
      (node (ref "D24") (pin "3") (pinfunction "CK1_3") (pintype "passive"))
      (node (ref "IC8") (pin "18") (pinfunction "O1_18") (pintype "open_collector"))
    )
    (net (code "88") (name "SEG25") (class "Default")
      (node (ref "D25") (pin "3") (pinfunction "CK1_3") (pintype "passive"))
      (node (ref "IC9") (pin "11") (pinfunction "O8_11") (pintype "open_collector"))
    )
    (net (code "89") (name "SEG26") (class "Default")
      (node (ref "D26") (pin "3") (pinfunction "CK1_3") (pintype "passive"))
      (node (ref "IC9") (pin "12") (pinfunction "O7_12") (pintype "open_collector"))
    )
    (net (code "90") (name "SEG27") (class "Default")
      (node (ref "D27") (pin "3") (pinfunction "CK1_3") (pintype "passive"))
      (node (ref "IC9") (pin "13") (pinfunction "O6_13") (pintype "open_collector"))
    )
    (net (code "91") (name "SEG28") (class "Default")
      (node (ref "D28") (pin "3") (pinfunction "CK1_3") (pintype "passive"))
      (node (ref "IC9") (pin "14") (pinfunction "O5_14") (pintype "open_collector"))
    )
    (net (code "92") (name "SEG29") (class "Default")
      (node (ref "D29") (pin "3") (pinfunction "CK1_3") (pintype "passive"))
      (node (ref "IC9") (pin "15") (pinfunction "O4_15") (pintype "open_collector"))
    )
    (net (code "93") (name "SEG30") (class "Default")
      (node (ref "D30") (pin "3") (pinfunction "CK1_3") (pintype "passive"))
      (node (ref "IC9") (pin "16") (pinfunction "O3_16") (pintype "open_collector"))
    )
    (net (code "94") (name "SEG31") (class "Default")
      (node (ref "D31") (pin "3") (pinfunction "CK1_3") (pintype "passive"))
      (node (ref "IC9") (pin "17") (pinfunction "O2_17") (pintype "open_collector"))
    )
    (net (code "95") (name "SEG32") (class "Default")
      (node (ref "D32") (pin "3") (pinfunction "CK1_3") (pintype "passive"))
      (node (ref "IC9") (pin "18") (pinfunction "O1_18") (pintype "open_collector"))
    )
    (net (code "96") (name "SEG33") (class "Default")
      (node (ref "D33") (pin "3") (pinfunction "CK1_3") (pintype "passive"))
      (node (ref "IC10") (pin "11") (pinfunction "O8_11") (pintype "open_collector"))
    )
    (net (code "97") (name "SEG34") (class "Default")
      (node (ref "D34") (pin "3") (pinfunction "CK1_3") (pintype "passive"))
      (node (ref "IC10") (pin "12") (pinfunction "O7_12") (pintype "open_collector"))
    )
    (net (code "98") (name "SEG35") (class "Default")
      (node (ref "D35") (pin "3") (pinfunction "CK1_3") (pintype "passive"))
      (node (ref "IC10") (pin "13") (pinfunction "O6_13") (pintype "open_collector"))
    )
    (net (code "99") (name "SEG36") (class "Default")
      (node (ref "D36") (pin "3") (pinfunction "CK1_3") (pintype "passive"))
      (node (ref "IC10") (pin "14") (pinfunction "O5_14") (pintype "open_collector"))
    )
    (net (code "100") (name "SEG37") (class "Default")
      (node (ref "D37") (pin "3") (pinfunction "CK1_3") (pintype "passive"))
      (node (ref "IC10") (pin "15") (pinfunction "O4_15") (pintype "open_collector"))
    )
    (net (code "101") (name "SEG38") (class "Default")
      (node (ref "D38") (pin "3") (pinfunction "CK1_3") (pintype "passive"))
      (node (ref "IC10") (pin "16") (pinfunction "O3_16") (pintype "open_collector"))
    )
    (net (code "102") (name "SEG39") (class "Default")
      (node (ref "D39") (pin "3") (pinfunction "CK1_3") (pintype "passive"))
      (node (ref "IC10") (pin "17") (pinfunction "O2_17") (pintype "open_collector"))
    )
    (net (code "103") (name "SEG40") (class "Default")
      (node (ref "D40") (pin "3") (pinfunction "CK1_3") (pintype "passive"))
      (node (ref "IC10") (pin "18") (pinfunction "O1_18") (pintype "open_collector"))
    )
    (net (code "104") (name "SH_CP") (class "Default")
      (node (ref "IC1") (pin "11") (pinfunction "SCK_11") (pintype "input"))
      (node (ref "IC2") (pin "11") (pinfunction "SCK_11") (pintype "input"))
      (node (ref "IC3") (pin "11") (pinfunction "SCK_11") (pintype "input"))
      (node (ref "IC4") (pin "11") (pinfunction "SCK_11") (pintype "input"))
      (node (ref "IC5") (pin "11") (pinfunction "SCK_11") (pintype "input"))
    )
    (net (code "105") (name "ST_CP") (class "Default")
      (node (ref "IC1") (pin "12") (pinfunction "RCK_12") (pintype "input"))
      (node (ref "IC2") (pin "12") (pinfunction "RCK_12") (pintype "input"))
      (node (ref "IC3") (pin "12") (pinfunction "RCK_12") (pintype "input"))
      (node (ref "IC4") (pin "12") (pinfunction "RCK_12") (pintype "input"))
      (node (ref "IC5") (pin "12") (pinfunction "RCK_12") (pintype "input"))
    )
    (net (code "106") (name "VCC") (class "Default")
      (node (ref "IC1") (pin "16") (pinfunction "VCC_16") (pintype "power_in"))
      (node (ref "IC10") (pin "10") (pinfunction "CD+_10") (pintype "passive"))
      (node (ref "IC2") (pin "16") (pinfunction "VCC_16") (pintype "power_in"))
      (node (ref "IC3") (pin "16") (pinfunction "VCC_16") (pintype "power_in"))
      (node (ref "IC4") (pin "16") (pinfunction "VCC_16") (pintype "power_in"))
      (node (ref "IC5") (pin "16") (pinfunction "VCC_16") (pintype "power_in"))
      (node (ref "IC6") (pin "10") (pinfunction "CD+_10") (pintype "passive"))
      (node (ref "IC7") (pin "10") (pinfunction "CD+_10") (pintype "passive"))
      (node (ref "IC8") (pin "10") (pinfunction "CD+_10") (pintype "passive"))
      (node (ref "IC9") (pin "10") (pinfunction "CD+_10") (pintype "passive"))
      (node (ref "T1") (pin "3") (pinfunction "C_3") (pintype "passive"))
      (node (ref "T2") (pin "3") (pinfunction "C_3") (pintype "passive"))
      (node (ref "T3") (pin "3") (pinfunction "C_3") (pintype "passive"))
      (node (ref "T4") (pin "3") (pinfunction "C_3") (pintype "passive"))
      (node (ref "T5") (pin "3") (pinfunction "C_3") (pintype "passive"))
      (node (ref "T6") (pin "3") (pinfunction "C_3") (pintype "passive"))
      (node (ref "T7") (pin "3") (pinfunction "C_3") (pintype "passive"))
      (node (ref "T8") (pin "3") (pinfunction "C_3") (pintype "passive"))
    )
    (net (code "107") (name "unconnected-(D1-CK2-Pad8)") (class "Default")
      (node (ref "D1") (pin "8") (pinfunction "CK2_8") (pintype "passive"))
    )
    (net (code "108") (name "unconnected-(D2-CK2-Pad8)") (class "Default")
      (node (ref "D2") (pin "8") (pinfunction "CK2_8") (pintype "passive"))
    )
    (net (code "109") (name "unconnected-(D3-CK2-Pad8)") (class "Default")
      (node (ref "D3") (pin "8") (pinfunction "CK2_8") (pintype "passive"))
    )
    (net (code "110") (name "unconnected-(D4-CK2-Pad8)") (class "Default")
      (node (ref "D4") (pin "8") (pinfunction "CK2_8") (pintype "passive"))
    )
    (net (code "111") (name "unconnected-(D5-CK2-Pad8)") (class "Default")
      (node (ref "D5") (pin "8") (pinfunction "CK2_8") (pintype "passive"))
    )
    (net (code "112") (name "unconnected-(D6-CK2-Pad8)") (class "Default")
      (node (ref "D6") (pin "8") (pinfunction "CK2_8") (pintype "passive"))
    )
    (net (code "113") (name "unconnected-(D7-CK2-Pad8)") (class "Default")
      (node (ref "D7") (pin "8") (pinfunction "CK2_8") (pintype "passive"))
    )
    (net (code "114") (name "unconnected-(D8-CK2-Pad8)") (class "Default")
      (node (ref "D8") (pin "8") (pinfunction "CK2_8") (pintype "passive"))
    )
    (net (code "115") (name "unconnected-(D9-CK2-Pad8)") (class "Default")
      (node (ref "D9") (pin "8") (pinfunction "CK2_8") (pintype "passive"))
    )
    (net (code "116") (name "unconnected-(D10-CK2-Pad8)") (class "Default")
      (node (ref "D10") (pin "8") (pinfunction "CK2_8") (pintype "passive"))
    )
    (net (code "117") (name "unconnected-(D11-CK2-Pad8)") (class "Default")
      (node (ref "D11") (pin "8") (pinfunction "CK2_8") (pintype "passive"))
    )
    (net (code "118") (name "unconnected-(D12-CK2-Pad8)") (class "Default")
      (node (ref "D12") (pin "8") (pinfunction "CK2_8") (pintype "passive"))
    )
    (net (code "119") (name "unconnected-(D13-CK2-Pad8)") (class "Default")
      (node (ref "D13") (pin "8") (pinfunction "CK2_8") (pintype "passive"))
    )
    (net (code "120") (name "unconnected-(D14-CK2-Pad8)") (class "Default")
      (node (ref "D14") (pin "8") (pinfunction "CK2_8") (pintype "passive"))
    )
    (net (code "121") (name "unconnected-(D15-CK2-Pad8)") (class "Default")
      (node (ref "D15") (pin "8") (pinfunction "CK2_8") (pintype "passive"))
    )
    (net (code "122") (name "unconnected-(D16-CK2-Pad8)") (class "Default")
      (node (ref "D16") (pin "8") (pinfunction "CK2_8") (pintype "passive"))
    )
    (net (code "123") (name "unconnected-(D17-CK2-Pad8)") (class "Default")
      (node (ref "D17") (pin "8") (pinfunction "CK2_8") (pintype "passive"))
    )
    (net (code "124") (name "unconnected-(D18-CK2-Pad8)") (class "Default")
      (node (ref "D18") (pin "8") (pinfunction "CK2_8") (pintype "passive"))
    )
    (net (code "125") (name "unconnected-(D19-CK2-Pad8)") (class "Default")
      (node (ref "D19") (pin "8") (pinfunction "CK2_8") (pintype "passive"))
    )
    (net (code "126") (name "unconnected-(D20-CK2-Pad8)") (class "Default")
      (node (ref "D20") (pin "8") (pinfunction "CK2_8") (pintype "passive"))
    )
    (net (code "127") (name "unconnected-(D21-CK2-Pad8)") (class "Default")
      (node (ref "D21") (pin "8") (pinfunction "CK2_8") (pintype "passive"))
    )
    (net (code "128") (name "unconnected-(D22-CK2-Pad8)") (class "Default")
      (node (ref "D22") (pin "8") (pinfunction "CK2_8") (pintype "passive"))
    )
    (net (code "129") (name "unconnected-(D23-CK2-Pad8)") (class "Default")
      (node (ref "D23") (pin "8") (pinfunction "CK2_8") (pintype "passive"))
    )
    (net (code "130") (name "unconnected-(D24-CK2-Pad8)") (class "Default")
      (node (ref "D24") (pin "8") (pinfunction "CK2_8") (pintype "passive"))
    )
    (net (code "131") (name "unconnected-(D25-CK2-Pad8)") (class "Default")
      (node (ref "D25") (pin "8") (pinfunction "CK2_8") (pintype "passive"))
    )
    (net (code "132") (name "unconnected-(D26-CK2-Pad8)") (class "Default")
      (node (ref "D26") (pin "8") (pinfunction "CK2_8") (pintype "passive"))
    )
    (net (code "133") (name "unconnected-(D27-CK2-Pad8)") (class "Default")
      (node (ref "D27") (pin "8") (pinfunction "CK2_8") (pintype "passive"))
    )
    (net (code "134") (name "unconnected-(D28-CK2-Pad8)") (class "Default")
      (node (ref "D28") (pin "8") (pinfunction "CK2_8") (pintype "passive"))
    )
    (net (code "135") (name "unconnected-(D29-CK2-Pad8)") (class "Default")
      (node (ref "D29") (pin "8") (pinfunction "CK2_8") (pintype "passive"))
    )
    (net (code "136") (name "unconnected-(D30-CK2-Pad8)") (class "Default")
      (node (ref "D30") (pin "8") (pinfunction "CK2_8") (pintype "passive"))
    )
    (net (code "137") (name "unconnected-(D31-CK2-Pad8)") (class "Default")
      (node (ref "D31") (pin "8") (pinfunction "CK2_8") (pintype "passive"))
    )
    (net (code "138") (name "unconnected-(D32-CK2-Pad8)") (class "Default")
      (node (ref "D32") (pin "8") (pinfunction "CK2_8") (pintype "passive"))
    )
    (net (code "139") (name "unconnected-(D33-CK2-Pad8)") (class "Default")
      (node (ref "D33") (pin "8") (pinfunction "CK2_8") (pintype "passive"))
    )
    (net (code "140") (name "unconnected-(D34-CK2-Pad8)") (class "Default")
      (node (ref "D34") (pin "8") (pinfunction "CK2_8") (pintype "passive"))
    )
    (net (code "141") (name "unconnected-(D35-CK2-Pad8)") (class "Default")
      (node (ref "D35") (pin "8") (pinfunction "CK2_8") (pintype "passive"))
    )
    (net (code "142") (name "unconnected-(D36-CK2-Pad8)") (class "Default")
      (node (ref "D36") (pin "8") (pinfunction "CK2_8") (pintype "passive"))
    )
    (net (code "143") (name "unconnected-(D37-CK2-Pad8)") (class "Default")
      (node (ref "D37") (pin "8") (pinfunction "CK2_8") (pintype "passive"))
    )
    (net (code "144") (name "unconnected-(D38-CK2-Pad8)") (class "Default")
      (node (ref "D38") (pin "8") (pinfunction "CK2_8") (pintype "passive"))
    )
    (net (code "145") (name "unconnected-(D39-CK2-Pad8)") (class "Default")
      (node (ref "D39") (pin "8") (pinfunction "CK2_8") (pintype "passive"))
    )
    (net (code "146") (name "unconnected-(D40-CK2-Pad8)") (class "Default")
      (node (ref "D40") (pin "8") (pinfunction "CK2_8") (pintype "passive"))
    )
    (net (code "147") (name "unconnected-(IC5A-QH*-Pad9)") (class "Default")
      (node (ref "IC5") (pin "9") (pinfunction "QH*_9") (pintype "tri_state"))
    )
  )
)
